# sch_AGV_Output.net
KiCad netlist of a schematic drawn in Altium Designer
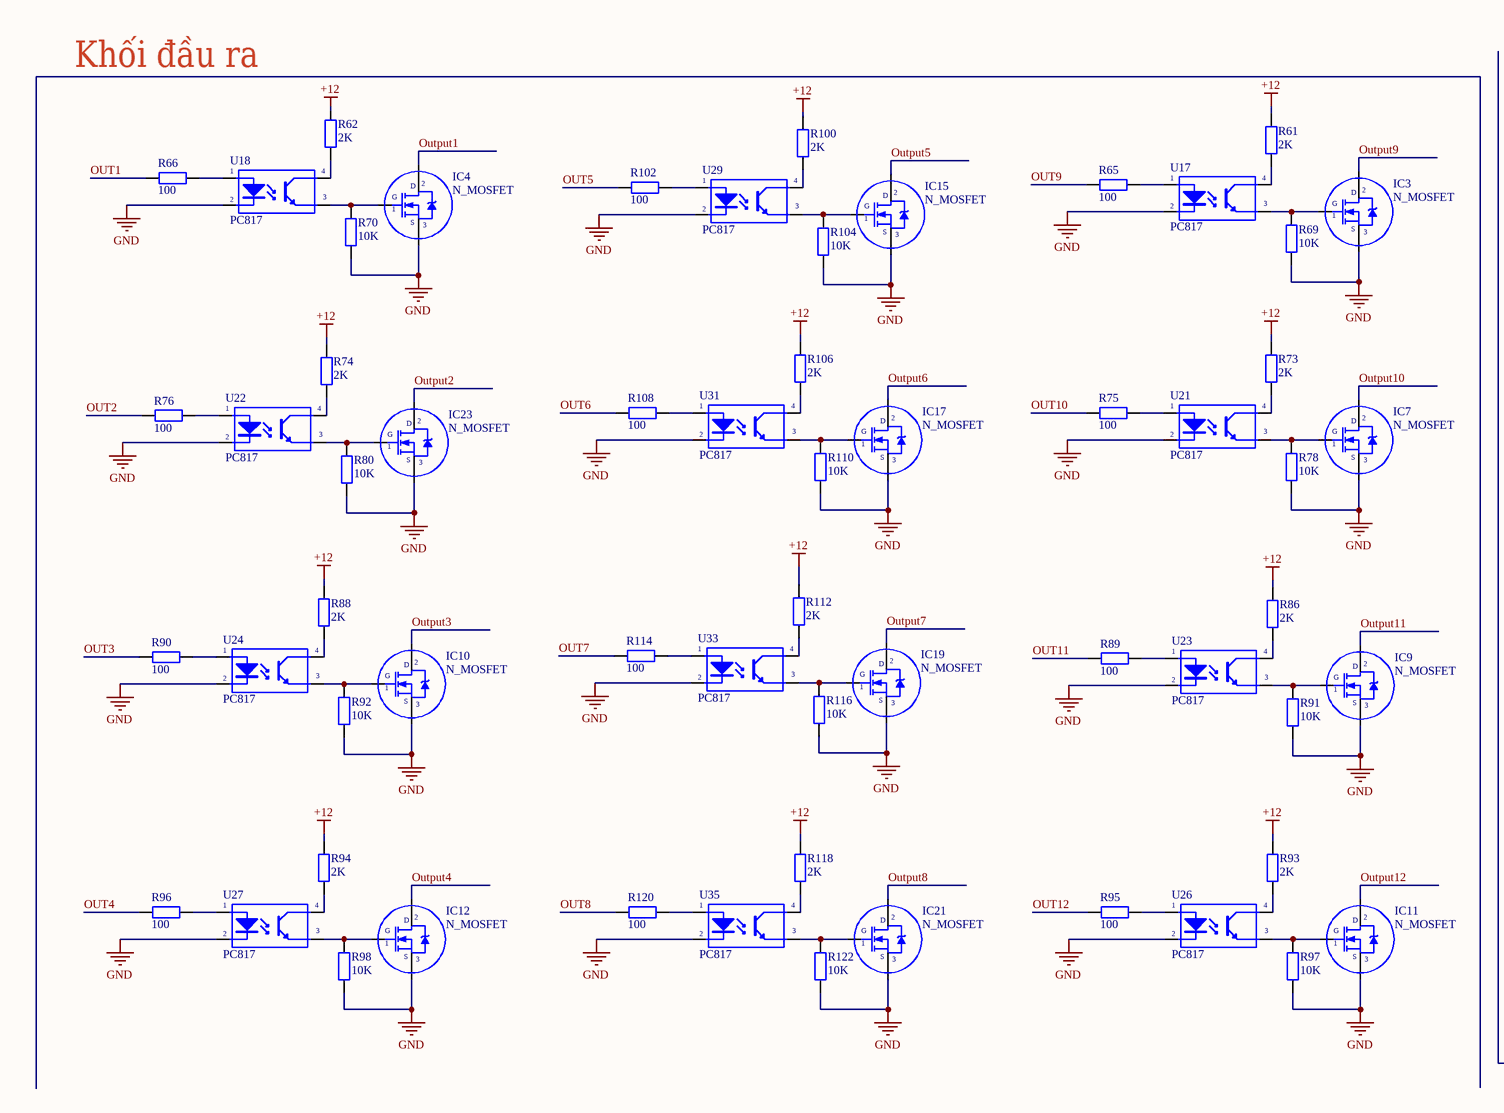
[diagram p0: sch_AGV_Output.SchDoc, left]
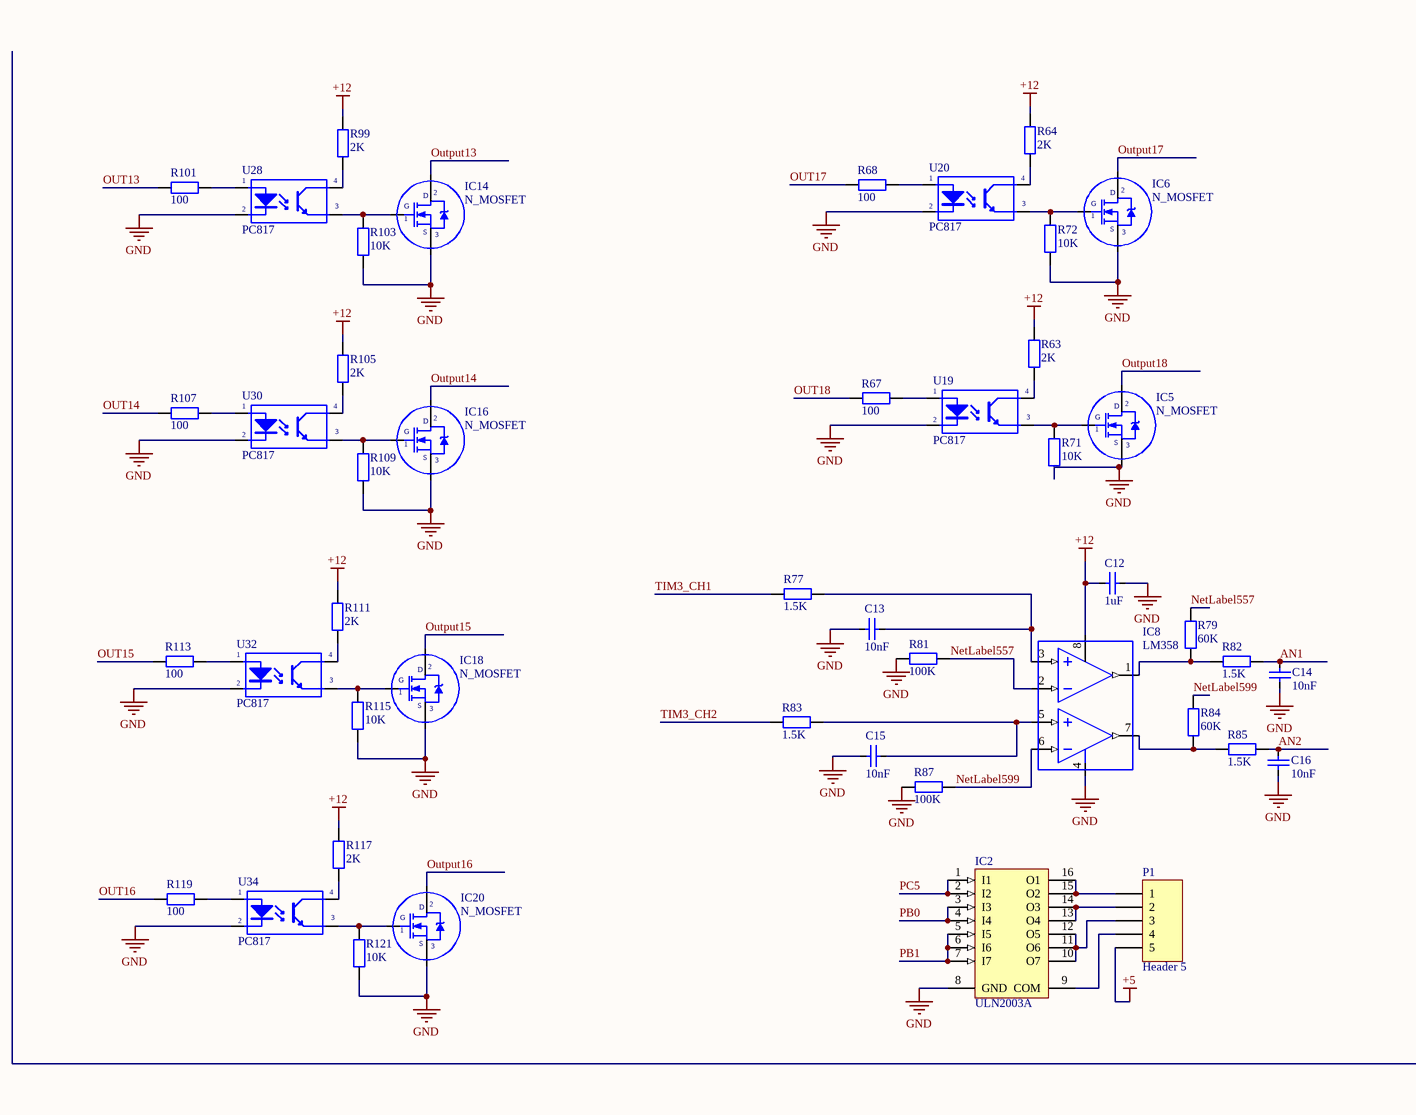
[diagram p1: sch_AGV_Output.SchDoc, right]

(export (version "E")
  (design (tool "Eeschema 10.0.6"))
  (components
    (comp (ref "C12")
      (value "1uF")
      (footprint "CAP_0805")
      (description "Capacitor")
      (fields (field (name "PUBLISHER") "Altium Limited"))
      (libsource (lib "schelib_AGVcontrol") (part "CapSMD"))
    )
    (comp (ref "C13")
      (value "10nF")
      (footprint "CAP_0805")
      (description "Capacitor")
      (fields (field (name "PUBLISHER") "Altium Limited"))
      (libsource (lib "schelib_AGVcontrol") (part "CapSMD"))
    )
    (comp (ref "C14")
      (value "10nF")
      (footprint "CAP_0805")
      (description "Capacitor")
      (fields (field (name "PUBLISHER") "Altium Limited"))
      (libsource (lib "schelib_AGVcontrol") (part "CapSMD"))
    )
    (comp (ref "C15")
      (value "10nF")
      (footprint "CAP_0805")
      (description "Capacitor")
      (fields (field (name "PUBLISHER") "Altium Limited"))
      (libsource (lib "schelib_AGVcontrol") (part "CapSMD"))
    )
    (comp (ref "C16")
      (value "10nF")
      (footprint "CAP_0805")
      (description "Capacitor")
      (fields (field (name "PUBLISHER") "Altium Limited"))
      (libsource (lib "schelib_AGVcontrol") (part "CapSMD"))
    )
    (comp (ref "IC2")
      (value "ULN2003A")
      (footprint "SOIC16")
      (description "High-Voltage, High-Current Darlington Array")
      (fields (field (name "PUBLISHER") "Altium Limited"))
      (libsource (lib "schelib_AGVcontrol") (part "ULN2003A"))
    )
    (comp (ref "IC3")
      (value "N_MOSFET")
      (footprint "SOT23A")
      (description "Generic N Channel MOSFET")
      (libsource (lib "schelib_AGVcontrol") (part "MOSFET_N"))
    )
    (comp (ref "IC4")
      (value "N_MOSFET")
      (footprint "SOT23A")
      (description "Generic N Channel MOSFET")
      (libsource (lib "schelib_AGVcontrol") (part "MOSFET_N"))
    )
    (comp (ref "IC5")
      (value "N_MOSFET")
      (footprint "SOT23A")
      (description "Generic N Channel MOSFET")
      (libsource (lib "schelib_AGVcontrol") (part "MOSFET_N"))
    )
    (comp (ref "IC6")
      (value "N_MOSFET")
      (footprint "SOT23A")
      (description "Generic N Channel MOSFET")
      (libsource (lib "schelib_AGVcontrol") (part "MOSFET_N"))
    )
    (comp (ref "IC7")
      (value "N_MOSFET")
      (footprint "SOT23A")
      (description "Generic N Channel MOSFET")
      (libsource (lib "schelib_AGVcontrol") (part "MOSFET_N"))
    )
    (comp (ref "IC8")
      (value "LM358")
      (footprint "SOP8-PP")
      (description "Low-Power Dual Operational Amplifier")
      (libsource (lib "schelib_AGVcontrol") (part "LM358"))
    )
    (comp (ref "IC9")
      (value "N_MOSFET")
      (footprint "SOT23A")
      (description "Generic N Channel MOSFET")
      (libsource (lib "schelib_AGVcontrol") (part "MOSFET_N"))
    )
    (comp (ref "IC10")
      (value "N_MOSFET")
      (footprint "SOT23A")
      (description "Generic N Channel MOSFET")
      (libsource (lib "schelib_AGVcontrol") (part "MOSFET_N"))
    )
    (comp (ref "IC11")
      (value "N_MOSFET")
      (footprint "SOT23A")
      (description "Generic N Channel MOSFET")
      (libsource (lib "schelib_AGVcontrol") (part "MOSFET_N"))
    )
    (comp (ref "IC12")
      (value "N_MOSFET")
      (footprint "SOT23A")
      (description "Generic N Channel MOSFET")
      (libsource (lib "schelib_AGVcontrol") (part "MOSFET_N"))
    )
    (comp (ref "IC14")
      (value "N_MOSFET")
      (footprint "SOT23A")
      (description "Generic N Channel MOSFET")
      (libsource (lib "schelib_AGVcontrol") (part "MOSFET_N"))
    )
    (comp (ref "IC15")
      (value "N_MOSFET")
      (footprint "SOT23A")
      (description "Generic N Channel MOSFET")
      (libsource (lib "schelib_AGVcontrol") (part "MOSFET_N"))
    )
    (comp (ref "IC16")
      (value "N_MOSFET")
      (footprint "SOT23A")
      (description "Generic N Channel MOSFET")
      (libsource (lib "schelib_AGVcontrol") (part "MOSFET_N"))
    )
    (comp (ref "IC17")
      (value "N_MOSFET")
      (footprint "SOT23A")
      (description "Generic N Channel MOSFET")
      (libsource (lib "schelib_AGVcontrol") (part "MOSFET_N"))
    )
    (comp (ref "IC18")
      (value "N_MOSFET")
      (footprint "SOT23A")
      (description "Generic N Channel MOSFET")
      (libsource (lib "schelib_AGVcontrol") (part "MOSFET_N"))
    )
    (comp (ref "IC19")
      (value "N_MOSFET")
      (footprint "SOT23A")
      (description "Generic N Channel MOSFET")
      (libsource (lib "schelib_AGVcontrol") (part "MOSFET_N"))
    )
    (comp (ref "IC20")
      (value "N_MOSFET")
      (footprint "SOT23A")
      (description "Generic N Channel MOSFET")
      (libsource (lib "schelib_AGVcontrol") (part "MOSFET_N"))
    )
    (comp (ref "IC21")
      (value "N_MOSFET")
      (footprint "SOT23A")
      (description "Generic N Channel MOSFET")
      (libsource (lib "schelib_AGVcontrol") (part "MOSFET_N"))
    )
    (comp (ref "IC23")
      (value "N_MOSFET")
      (footprint "SOT23A")
      (description "Generic N Channel MOSFET")
      (libsource (lib "schelib_AGVcontrol") (part "MOSFET_N"))
    )
    (comp (ref "P1")
      (value "Header 5")
      (footprint "HDR5")
      (description "Header, 5-Pin")
      (fields (field (name "PUBLISHER") "Altium Limited"))
      (libsource (lib "schelib_AGVcontrol") (part "Header 5"))
    )
    (comp (ref "R61")
      (value "2K")
      (footprint "RES_SMD_0805")
      (description "Resistor")
      (fields
        (field (name "MANUFACTURER") "Generic Components")
        (field (name "PUBLISHER") "Altium Hobart Technology Centre")
      )
      (libsource (lib "schelib_AGVcontrol") (part "Res"))
    )
    (comp (ref "R62")
      (value "2K")
      (footprint "RES_SMD_0805")
      (description "Resistor")
      (fields
        (field (name "MANUFACTURER") "Generic Components")
        (field (name "PUBLISHER") "Altium Hobart Technology Centre")
      )
      (libsource (lib "schelib_AGVcontrol") (part "Res"))
    )
    (comp (ref "R63")
      (value "2K")
      (footprint "RES_SMD_0805")
      (description "Resistor")
      (fields
        (field (name "MANUFACTURER") "Generic Components")
        (field (name "PUBLISHER") "Altium Hobart Technology Centre")
      )
      (libsource (lib "schelib_AGVcontrol") (part "Res"))
    )
    (comp (ref "R64")
      (value "2K")
      (footprint "RES_SMD_0805")
      (description "Resistor")
      (fields
        (field (name "MANUFACTURER") "Generic Components")
        (field (name "PUBLISHER") "Altium Hobart Technology Centre")
      )
      (libsource (lib "schelib_AGVcontrol") (part "Res"))
    )
    (comp (ref "R65")
      (value "100")
      (footprint "RES_SMD_0805")
      (description "Resistor")
      (fields
        (field (name "MANUFACTURER") "Generic Components")
        (field (name "PUBLISHER") "Altium Hobart Technology Centre")
      )
      (libsource (lib "schelib_AGVcontrol") (part "Res"))
    )
    (comp (ref "R66")
      (value "100")
      (footprint "RES_SMD_0805")
      (description "Resistor")
      (fields
        (field (name "MANUFACTURER") "Generic Components")
        (field (name "PUBLISHER") "Altium Hobart Technology Centre")
      )
      (libsource (lib "schelib_AGVcontrol") (part "Res"))
    )
    (comp (ref "R67")
      (value "100")
      (footprint "RES_SMD_0805")
      (description "Resistor")
      (fields
        (field (name "MANUFACTURER") "Generic Components")
        (field (name "PUBLISHER") "Altium Hobart Technology Centre")
      )
      (libsource (lib "schelib_AGVcontrol") (part "Res"))
    )
    (comp (ref "R68")
      (value "100")
      (footprint "RES_SMD_0805")
      (description "Resistor")
      (fields
        (field (name "MANUFACTURER") "Generic Components")
        (field (name "PUBLISHER") "Altium Hobart Technology Centre")
      )
      (libsource (lib "schelib_AGVcontrol") (part "Res"))
    )
    (comp (ref "R69")
      (value "10K")
      (footprint "RES_SMD_0805")
      (description "Resistor")
      (fields
        (field (name "MANUFACTURER") "Generic Components")
        (field (name "PUBLISHER") "Altium Hobart Technology Centre")
      )
      (libsource (lib "schelib_AGVcontrol") (part "Res"))
    )
    (comp (ref "R70")
      (value "10K")
      (footprint "RES_SMD_0805")
      (description "Resistor")
      (fields
        (field (name "MANUFACTURER") "Generic Components")
        (field (name "PUBLISHER") "Altium Hobart Technology Centre")
      )
      (libsource (lib "schelib_AGVcontrol") (part "Res"))
    )
    (comp (ref "R71")
      (value "10K")
      (footprint "RES_SMD_0805")
      (description "Resistor")
      (fields
        (field (name "MANUFACTURER") "Generic Components")
        (field (name "PUBLISHER") "Altium Hobart Technology Centre")
      )
      (libsource (lib "schelib_AGVcontrol") (part "Res"))
    )
    (comp (ref "R72")
      (value "10K")
      (footprint "RES_SMD_0805")
      (description "Resistor")
      (fields
        (field (name "MANUFACTURER") "Generic Components")
        (field (name "PUBLISHER") "Altium Hobart Technology Centre")
      )
      (libsource (lib "schelib_AGVcontrol") (part "Res"))
    )
    (comp (ref "R73")
      (value "2K")
      (footprint "RES_SMD_0805")
      (description "Resistor")
      (fields
        (field (name "MANUFACTURER") "Generic Components")
        (field (name "PUBLISHER") "Altium Hobart Technology Centre")
      )
      (libsource (lib "schelib_AGVcontrol") (part "Res"))
    )
    (comp (ref "R74")
      (value "2K")
      (footprint "RES_SMD_0805")
      (description "Resistor")
      (fields
        (field (name "MANUFACTURER") "Generic Components")
        (field (name "PUBLISHER") "Altium Hobart Technology Centre")
      )
      (libsource (lib "schelib_AGVcontrol") (part "Res"))
    )
    (comp (ref "R75")
      (value "100")
      (footprint "RES_SMD_0805")
      (description "Resistor")
      (fields
        (field (name "MANUFACTURER") "Generic Components")
        (field (name "PUBLISHER") "Altium Hobart Technology Centre")
      )
      (libsource (lib "schelib_AGVcontrol") (part "Res"))
    )
    (comp (ref "R76")
      (value "100")
      (footprint "RES_SMD_0805")
      (description "Resistor")
      (fields
        (field (name "MANUFACTURER") "Generic Components")
        (field (name "PUBLISHER") "Altium Hobart Technology Centre")
      )
      (libsource (lib "schelib_AGVcontrol") (part "Res"))
    )
    (comp (ref "R77")
      (value "1.5K")
      (footprint "RES_SMD_0805")
      (description "Resistor")
      (fields
        (field (name "MANUFACTURER") "Generic Components")
        (field (name "PUBLISHER") "Altium Hobart Technology Centre")
      )
      (libsource (lib "schelib_AGVcontrol") (part "Res"))
    )
    (comp (ref "R78")
      (value "10K")
      (footprint "RES_SMD_0805")
      (description "Resistor")
      (fields
        (field (name "MANUFACTURER") "Generic Components")
        (field (name "PUBLISHER") "Altium Hobart Technology Centre")
      )
      (libsource (lib "schelib_AGVcontrol") (part "Res"))
    )
    (comp (ref "R79")
      (value "60K")
      (footprint "RES_SMD_0805")
      (description "Resistor")
      (fields
        (field (name "MANUFACTURER") "Generic Components")
        (field (name "PUBLISHER") "Altium Hobart Technology Centre")
      )
      (libsource (lib "schelib_AGVcontrol") (part "Res"))
    )
    (comp (ref "R80")
      (value "10K")
      (footprint "RES_SMD_0805")
      (description "Resistor")
      (fields
        (field (name "MANUFACTURER") "Generic Components")
        (field (name "PUBLISHER") "Altium Hobart Technology Centre")
      )
      (libsource (lib "schelib_AGVcontrol") (part "Res"))
    )
    (comp (ref "R81")
      (value "100K")
      (footprint "RES_SMD_0805")
      (description "Resistor")
      (fields
        (field (name "MANUFACTURER") "Generic Components")
        (field (name "PUBLISHER") "Altium Hobart Technology Centre")
      )
      (libsource (lib "schelib_AGVcontrol") (part "Res"))
    )
    (comp (ref "R82")
      (value "1.5K")
      (footprint "RES_SMD_0805")
      (description "Resistor")
      (fields
        (field (name "MANUFACTURER") "Generic Components")
        (field (name "PUBLISHER") "Altium Hobart Technology Centre")
      )
      (libsource (lib "schelib_AGVcontrol") (part "Res"))
    )
    (comp (ref "R83")
      (value "1.5K")
      (footprint "RES_SMD_0805")
      (description "Resistor")
      (fields
        (field (name "MANUFACTURER") "Generic Components")
        (field (name "PUBLISHER") "Altium Hobart Technology Centre")
      )
      (libsource (lib "schelib_AGVcontrol") (part "Res"))
    )
    (comp (ref "R84")
      (value "60K")
      (footprint "RES_SMD_0805")
      (description "Resistor")
      (fields
        (field (name "MANUFACTURER") "Generic Components")
        (field (name "PUBLISHER") "Altium Hobart Technology Centre")
      )
      (libsource (lib "schelib_AGVcontrol") (part "Res"))
    )
    (comp (ref "R85")
      (value "1.5K")
      (footprint "RES_SMD_0805")
      (description "Resistor")
      (fields
        (field (name "MANUFACTURER") "Generic Components")
        (field (name "PUBLISHER") "Altium Hobart Technology Centre")
      )
      (libsource (lib "schelib_AGVcontrol") (part "Res"))
    )
    (comp (ref "R86")
      (value "2K")
      (footprint "RES_SMD_0805")
      (description "Resistor")
      (fields
        (field (name "MANUFACTURER") "Generic Components")
        (field (name "PUBLISHER") "Altium Hobart Technology Centre")
      )
      (libsource (lib "schelib_AGVcontrol") (part "Res"))
    )
    (comp (ref "R87")
      (value "100K")
      (footprint "RES_SMD_0805")
      (description "Resistor")
      (fields
        (field (name "MANUFACTURER") "Generic Components")
        (field (name "PUBLISHER") "Altium Hobart Technology Centre")
      )
      (libsource (lib "schelib_AGVcontrol") (part "Res"))
    )
    (comp (ref "R88")
      (value "2K")
      (footprint "RES_SMD_0805")
      (description "Resistor")
      (fields
        (field (name "MANUFACTURER") "Generic Components")
        (field (name "PUBLISHER") "Altium Hobart Technology Centre")
      )
      (libsource (lib "schelib_AGVcontrol") (part "Res"))
    )
    (comp (ref "R89")
      (value "100")
      (footprint "RES_SMD_0805")
      (description "Resistor")
      (fields
        (field (name "MANUFACTURER") "Generic Components")
        (field (name "PUBLISHER") "Altium Hobart Technology Centre")
      )
      (libsource (lib "schelib_AGVcontrol") (part "Res"))
    )
    (comp (ref "R90")
      (value "100")
      (footprint "RES_SMD_0805")
      (description "Resistor")
      (fields
        (field (name "MANUFACTURER") "Generic Components")
        (field (name "PUBLISHER") "Altium Hobart Technology Centre")
      )
      (libsource (lib "schelib_AGVcontrol") (part "Res"))
    )
    (comp (ref "R91")
      (value "10K")
      (footprint "RES_SMD_0805")
      (description "Resistor")
      (fields
        (field (name "MANUFACTURER") "Generic Components")
        (field (name "PUBLISHER") "Altium Hobart Technology Centre")
      )
      (libsource (lib "schelib_AGVcontrol") (part "Res"))
    )
    (comp (ref "R92")
      (value "10K")
      (footprint "RES_SMD_0805")
      (description "Resistor")
      (fields
        (field (name "MANUFACTURER") "Generic Components")
        (field (name "PUBLISHER") "Altium Hobart Technology Centre")
      )
      (libsource (lib "schelib_AGVcontrol") (part "Res"))
    )
    (comp (ref "R93")
      (value "2K")
      (footprint "RES_SMD_0805")
      (description "Resistor")
      (fields
        (field (name "MANUFACTURER") "Generic Components")
        (field (name "PUBLISHER") "Altium Hobart Technology Centre")
      )
      (libsource (lib "schelib_AGVcontrol") (part "Res"))
    )
    (comp (ref "R94")
      (value "2K")
      (footprint "RES_SMD_0805")
      (description "Resistor")
      (fields
        (field (name "MANUFACTURER") "Generic Components")
        (field (name "PUBLISHER") "Altium Hobart Technology Centre")
      )
      (libsource (lib "schelib_AGVcontrol") (part "Res"))
    )
    (comp (ref "R95")
      (value "100")
      (footprint "RES_SMD_0805")
      (description "Resistor")
      (fields
        (field (name "MANUFACTURER") "Generic Components")
        (field (name "PUBLISHER") "Altium Hobart Technology Centre")
      )
      (libsource (lib "schelib_AGVcontrol") (part "Res"))
    )
    (comp (ref "R96")
      (value "100")
      (footprint "RES_SMD_0805")
      (description "Resistor")
      (fields
        (field (name "MANUFACTURER") "Generic Components")
        (field (name "PUBLISHER") "Altium Hobart Technology Centre")
      )
      (libsource (lib "schelib_AGVcontrol") (part "Res"))
    )
    (comp (ref "R97")
      (value "10K")
      (footprint "RES_SMD_0805")
      (description "Resistor")
      (fields
        (field (name "MANUFACTURER") "Generic Components")
        (field (name "PUBLISHER") "Altium Hobart Technology Centre")
      )
      (libsource (lib "schelib_AGVcontrol") (part "Res"))
    )
    (comp (ref "R98")
      (value "10K")
      (footprint "RES_SMD_0805")
      (description "Resistor")
      (fields
        (field (name "MANUFACTURER") "Generic Components")
        (field (name "PUBLISHER") "Altium Hobart Technology Centre")
      )
      (libsource (lib "schelib_AGVcontrol") (part "Res"))
    )
    (comp (ref "R99")
      (value "2K")
      (footprint "RES_SMD_0805")
      (description "Resistor")
      (fields
        (field (name "MANUFACTURER") "Generic Components")
        (field (name "PUBLISHER") "Altium Hobart Technology Centre")
      )
      (libsource (lib "schelib_AGVcontrol") (part "Res"))
    )
    (comp (ref "R100")
      (value "2K")
      (footprint "RES_SMD_0805")
      (description "Resistor")
      (fields
        (field (name "MANUFACTURER") "Generic Components")
        (field (name "PUBLISHER") "Altium Hobart Technology Centre")
      )
      (libsource (lib "schelib_AGVcontrol") (part "Res"))
    )
    (comp (ref "R101")
      (value "100")
      (footprint "RES_SMD_0805")
      (description "Resistor")
      (fields
        (field (name "MANUFACTURER") "Generic Components")
        (field (name "PUBLISHER") "Altium Hobart Technology Centre")
      )
      (libsource (lib "schelib_AGVcontrol") (part "Res"))
    )
    (comp (ref "R102")
      (value "100")
      (footprint "RES_SMD_0805")
      (description "Resistor")
      (fields
        (field (name "MANUFACTURER") "Generic Components")
        (field (name "PUBLISHER") "Altium Hobart Technology Centre")
      )
      (libsource (lib "schelib_AGVcontrol") (part "Res"))
    )
    (comp (ref "R103")
      (value "10K")
      (footprint "RES_SMD_0805")
      (description "Resistor")
      (fields
        (field (name "MANUFACTURER") "Generic Components")
        (field (name "PUBLISHER") "Altium Hobart Technology Centre")
      )
      (libsource (lib "schelib_AGVcontrol") (part "Res"))
    )
    (comp (ref "R104")
      (value "10K")
      (footprint "RES_SMD_0805")
      (description "Resistor")
      (fields
        (field (name "MANUFACTURER") "Generic Components")
        (field (name "PUBLISHER") "Altium Hobart Technology Centre")
      )
      (libsource (lib "schelib_AGVcontrol") (part "Res"))
    )
    (comp (ref "R105")
      (value "2K")
      (footprint "RES_SMD_0805")
      (description "Resistor")
      (fields
        (field (name "MANUFACTURER") "Generic Components")
        (field (name "PUBLISHER") "Altium Hobart Technology Centre")
      )
      (libsource (lib "schelib_AGVcontrol") (part "Res"))
    )
    (comp (ref "R106")
      (value "2K")
      (footprint "RES_SMD_0805")
      (description "Resistor")
      (fields
        (field (name "MANUFACTURER") "Generic Components")
        (field (name "PUBLISHER") "Altium Hobart Technology Centre")
      )
      (libsource (lib "schelib_AGVcontrol") (part "Res"))
    )
    (comp (ref "R107")
      (value "100")
      (footprint "RES_SMD_0805")
      (description "Resistor")
      (fields
        (field (name "MANUFACTURER") "Generic Components")
        (field (name "PUBLISHER") "Altium Hobart Technology Centre")
      )
      (libsource (lib "schelib_AGVcontrol") (part "Res"))
    )
    (comp (ref "R108")
      (value "100")
      (footprint "RES_SMD_0805")
      (description "Resistor")
      (fields
        (field (name "MANUFACTURER") "Generic Components")
        (field (name "PUBLISHER") "Altium Hobart Technology Centre")
      )
      (libsource (lib "schelib_AGVcontrol") (part "Res"))
    )
    (comp (ref "R109")
      (value "10K")
      (footprint "RES_SMD_0805")
      (description "Resistor")
      (fields
        (field (name "MANUFACTURER") "Generic Components")
        (field (name "PUBLISHER") "Altium Hobart Technology Centre")
      )
      (libsource (lib "schelib_AGVcontrol") (part "Res"))
    )
    (comp (ref "R110")
      (value "10K")
      (footprint "RES_SMD_0805")
      (description "Resistor")
      (fields
        (field (name "MANUFACTURER") "Generic Components")
        (field (name "PUBLISHER") "Altium Hobart Technology Centre")
      )
      (libsource (lib "schelib_AGVcontrol") (part "Res"))
    )
    (comp (ref "R111")
      (value "2K")
      (footprint "RES_SMD_0805")
      (description "Resistor")
      (fields
        (field (name "MANUFACTURER") "Generic Components")
        (field (name "PUBLISHER") "Altium Hobart Technology Centre")
      )
      (libsource (lib "schelib_AGVcontrol") (part "Res"))
    )
    (comp (ref "R112")
      (value "2K")
      (footprint "RES_SMD_0805")
      (description "Resistor")
      (fields
        (field (name "MANUFACTURER") "Generic Components")
        (field (name "PUBLISHER") "Altium Hobart Technology Centre")
      )
      (libsource (lib "schelib_AGVcontrol") (part "Res"))
    )
    (comp (ref "R113")
      (value "100")
      (footprint "RES_SMD_0805")
      (description "Resistor")
      (fields
        (field (name "MANUFACTURER") "Generic Components")
        (field (name "PUBLISHER") "Altium Hobart Technology Centre")
      )
      (libsource (lib "schelib_AGVcontrol") (part "Res"))
    )
    (comp (ref "R114")
      (value "100")
      (footprint "RES_SMD_0805")
      (description "Resistor")
      (fields
        (field (name "MANUFACTURER") "Generic Components")
        (field (name "PUBLISHER") "Altium Hobart Technology Centre")
      )
      (libsource (lib "schelib_AGVcontrol") (part "Res"))
    )
    (comp (ref "R115")
      (value "10K")
      (footprint "RES_SMD_0805")
      (description "Resistor")
      (fields
        (field (name "MANUFACTURER") "Generic Components")
        (field (name "PUBLISHER") "Altium Hobart Technology Centre")
      )
      (libsource (lib "schelib_AGVcontrol") (part "Res"))
    )
    (comp (ref "R116")
      (value "10K")
      (footprint "RES_SMD_0805")
      (description "Resistor")
      (fields
        (field (name "MANUFACTURER") "Generic Components")
        (field (name "PUBLISHER") "Altium Hobart Technology Centre")
      )
      (libsource (lib "schelib_AGVcontrol") (part "Res"))
    )
    (comp (ref "R117")
      (value "2K")
      (footprint "RES_SMD_0805")
      (description "Resistor")
      (fields
        (field (name "MANUFACTURER") "Generic Components")
        (field (name "PUBLISHER") "Altium Hobart Technology Centre")
      )
      (libsource (lib "schelib_AGVcontrol") (part "Res"))
    )
    (comp (ref "R118")
      (value "2K")
      (footprint "RES_SMD_0805")
      (description "Resistor")
      (fields
        (field (name "MANUFACTURER") "Generic Components")
        (field (name "PUBLISHER") "Altium Hobart Technology Centre")
      )
      (libsource (lib "schelib_AGVcontrol") (part "Res"))
    )
    (comp (ref "R119")
      (value "100")
      (footprint "RES_SMD_0805")
      (description "Resistor")
      (fields
        (field (name "MANUFACTURER") "Generic Components")
        (field (name "PUBLISHER") "Altium Hobart Technology Centre")
      )
      (libsource (lib "schelib_AGVcontrol") (part "Res"))
    )
    (comp (ref "R120")
      (value "100")
      (footprint "RES_SMD_0805")
      (description "Resistor")
      (fields
        (field (name "MANUFACTURER") "Generic Components")
        (field (name "PUBLISHER") "Altium Hobart Technology Centre")
      )
      (libsource (lib "schelib_AGVcontrol") (part "Res"))
    )
    (comp (ref "R121")
      (value "10K")
      (footprint "RES_SMD_0805")
      (description "Resistor")
      (fields
        (field (name "MANUFACTURER") "Generic Components")
        (field (name "PUBLISHER") "Altium Hobart Technology Centre")
      )
      (libsource (lib "schelib_AGVcontrol") (part "Res"))
    )
    (comp (ref "R122")
      (value "10K")
      (footprint "RES_SMD_0805")
      (description "Resistor")
      (fields
        (field (name "MANUFACTURER") "Generic Components")
        (field (name "PUBLISHER") "Altium Hobart Technology Centre")
      )
      (libsource (lib "schelib_AGVcontrol") (part "Res"))
    )
    (comp (ref "U17")
      (value "PC817")
      (footprint "DIP4/W0.3")
      (description "Single Opto")
      (libsource (lib "schelib_AGVcontrol") (part "PC817"))
    )
    (comp (ref "U18")
      (value "PC817")
      (footprint "DIP4/W0.3")
      (description "Single Opto")
      (libsource (lib "schelib_AGVcontrol") (part "PC817"))
    )
    (comp (ref "U19")
      (value "PC817")
      (footprint "DIP4/W0.3")
      (description "Single Opto")
      (libsource (lib "schelib_AGVcontrol") (part "PC817"))
    )
    (comp (ref "U20")
      (value "PC817")
      (footprint "DIP4/W0.3")
      (description "Single Opto")
      (libsource (lib "schelib_AGVcontrol") (part "PC817"))
    )
    (comp (ref "U21")
      (value "PC817")
      (footprint "DIP4/W0.3")
      (description "Single Opto")
      (libsource (lib "schelib_AGVcontrol") (part "PC817"))
    )
    (comp (ref "U22")
      (value "PC817")
      (footprint "DIP4/W0.3")
      (description "Single Opto")
      (libsource (lib "schelib_AGVcontrol") (part "PC817"))
    )
    (comp (ref "U23")
      (value "PC817")
      (footprint "DIP4/W0.3")
      (description "Single Opto")
      (libsource (lib "schelib_AGVcontrol") (part "PC817"))
    )
    (comp (ref "U24")
      (value "PC817")
      (footprint "DIP4/W0.3")
      (description "Single Opto")
      (libsource (lib "schelib_AGVcontrol") (part "PC817"))
    )
    (comp (ref "U26")
      (value "PC817")
      (footprint "DIP4/W0.3")
      (description "Single Opto")
      (libsource (lib "schelib_AGVcontrol") (part "PC817"))
    )
    (comp (ref "U27")
      (value "PC817")
      (footprint "DIP4/W0.3")
      (description "Single Opto")
      (libsource (lib "schelib_AGVcontrol") (part "PC817"))
    )
    (comp (ref "U28")
      (value "PC817")
      (footprint "DIP4/W0.3")
      (description "Single Opto")
      (libsource (lib "schelib_AGVcontrol") (part "PC817"))
    )
    (comp (ref "U29")
      (value "PC817")
      (footprint "DIP4/W0.3")
      (description "Single Opto")
      (libsource (lib "schelib_AGVcontrol") (part "PC817"))
    )
    (comp (ref "U30")
      (value "PC817")
      (footprint "DIP4/W0.3")
      (description "Single Opto")
      (libsource (lib "schelib_AGVcontrol") (part "PC817"))
    )
    (comp (ref "U31")
      (value "PC817")
      (footprint "DIP4/W0.3")
      (description "Single Opto")
      (libsource (lib "schelib_AGVcontrol") (part "PC817"))
    )
    (comp (ref "U32")
      (value "PC817")
      (footprint "DIP4/W0.3")
      (description "Single Opto")
      (libsource (lib "schelib_AGVcontrol") (part "PC817"))
    )
    (comp (ref "U33")
      (value "PC817")
      (footprint "DIP4/W0.3")
      (description "Single Opto")
      (libsource (lib "schelib_AGVcontrol") (part "PC817"))
    )
    (comp (ref "U34")
      (value "PC817")
      (footprint "DIP4/W0.3")
      (description "Single Opto")
      (libsource (lib "schelib_AGVcontrol") (part "PC817"))
    )
    (comp (ref "U35")
      (value "PC817")
      (footprint "DIP4/W0.3")
      (description "Single Opto")
      (libsource (lib "schelib_AGVcontrol") (part "PC817"))
    )
  )
  (nets
    (net (code "1") (name "+5") (class "Default")
      (node (ref "P1") (pin "5") (pinfunction "5_5") (pintype "passive"))
    )
    (net (code "2") (name "+12") (class "Default")
      (node (ref "C12") (pin "1") (pinfunction "1_1") (pintype "passive"))
      (node (ref "IC8") (pin "8") (pinfunction "+V_8") (pintype "passive"))
      (node (ref "R100") (pin "1") (pinfunction "1_1") (pintype "passive"))
      (node (ref "R105") (pin "1") (pinfunction "1_1") (pintype "passive"))
      (node (ref "R106") (pin "1") (pinfunction "1_1") (pintype "passive"))
      (node (ref "R111") (pin "1") (pinfunction "1_1") (pintype "passive"))
      (node (ref "R112") (pin "1") (pinfunction "1_1") (pintype "passive"))
      (node (ref "R117") (pin "1") (pinfunction "1_1") (pintype "passive"))
      (node (ref "R118") (pin "1") (pinfunction "1_1") (pintype "passive"))
      (node (ref "R61") (pin "1") (pinfunction "1_1") (pintype "passive"))
      (node (ref "R62") (pin "1") (pinfunction "1_1") (pintype "passive"))
      (node (ref "R63") (pin "1") (pinfunction "1_1") (pintype "passive"))
      (node (ref "R64") (pin "1") (pinfunction "1_1") (pintype "passive"))
      (node (ref "R73") (pin "1") (pinfunction "1_1") (pintype "passive"))
      (node (ref "R74") (pin "1") (pinfunction "1_1") (pintype "passive"))
      (node (ref "R86") (pin "1") (pinfunction "1_1") (pintype "passive"))
      (node (ref "R88") (pin "1") (pinfunction "1_1") (pintype "passive"))
      (node (ref "R93") (pin "1") (pinfunction "1_1") (pintype "passive"))
      (node (ref "R94") (pin "1") (pinfunction "1_1") (pintype "passive"))
      (node (ref "R99") (pin "1") (pinfunction "1_1") (pintype "passive"))
    )
    (net (code "3") (name "/AN1") (class "Default")
      (node (ref "C14") (pin "2") (pinfunction "2_2") (pintype "passive"))
      (node (ref "R82") (pin "1") (pinfunction "1_1") (pintype "passive"))
    )
    (net (code "4") (name "/AN2") (class "Default")
      (node (ref "C16") (pin "2") (pinfunction "2_2") (pintype "passive"))
      (node (ref "R85") (pin "1") (pinfunction "1_1") (pintype "passive"))
    )
    (net (code "5") (name "/NetLabel557") (class "Default")
      (node (ref "IC8") (pin "2") (pinfunction "IN-_2") (pintype "input"))
      (node (ref "R79") (pin "1") (pinfunction "1_1") (pintype "passive"))
      (node (ref "R81") (pin "1") (pinfunction "1_1") (pintype "passive"))
    )
    (net (code "6") (name "/NetLabel599") (class "Default")
      (node (ref "IC8") (pin "6") (pinfunction "IN-_6") (pintype "input"))
      (node (ref "R84") (pin "1") (pinfunction "1_1") (pintype "passive"))
      (node (ref "R87") (pin "1") (pinfunction "1_1") (pintype "passive"))
    )
    (net (code "7") (name "/OUT1") (class "Default")
      (node (ref "R66") (pin "2") (pinfunction "2_2") (pintype "passive"))
    )
    (net (code "8") (name "/OUT2") (class "Default")
      (node (ref "R76") (pin "2") (pinfunction "2_2") (pintype "passive"))
    )
    (net (code "9") (name "/OUT3") (class "Default")
      (node (ref "R90") (pin "2") (pinfunction "2_2") (pintype "passive"))
    )
    (net (code "10") (name "/OUT4") (class "Default")
      (node (ref "R96") (pin "2") (pinfunction "2_2") (pintype "passive"))
    )
    (net (code "11") (name "/OUT5") (class "Default")
      (node (ref "R102") (pin "2") (pinfunction "2_2") (pintype "passive"))
    )
    (net (code "12") (name "/OUT6") (class "Default")
      (node (ref "R108") (pin "2") (pinfunction "2_2") (pintype "passive"))
    )
    (net (code "13") (name "/OUT7") (class "Default")
      (node (ref "R114") (pin "2") (pinfunction "2_2") (pintype "passive"))
    )
    (net (code "14") (name "/OUT8") (class "Default")
      (node (ref "R120") (pin "2") (pinfunction "2_2") (pintype "passive"))
    )
    (net (code "15") (name "/OUT9") (class "Default")
      (node (ref "R65") (pin "2") (pinfunction "2_2") (pintype "passive"))
    )
    (net (code "16") (name "/OUT10") (class "Default")
      (node (ref "R75") (pin "2") (pinfunction "2_2") (pintype "passive"))
    )
    (net (code "17") (name "/OUT11") (class "Default")
      (node (ref "R89") (pin "2") (pinfunction "2_2") (pintype "passive"))
    )
    (net (code "18") (name "/OUT12") (class "Default")
      (node (ref "R95") (pin "2") (pinfunction "2_2") (pintype "passive"))
    )
    (net (code "19") (name "/OUT13") (class "Default")
      (node (ref "R101") (pin "2") (pinfunction "2_2") (pintype "passive"))
    )
    (net (code "20") (name "/OUT14") (class "Default")
      (node (ref "R107") (pin "2") (pinfunction "2_2") (pintype "passive"))
    )
    (net (code "21") (name "/OUT15") (class "Default")
      (node (ref "R113") (pin "2") (pinfunction "2_2") (pintype "passive"))
    )
    (net (code "22") (name "/OUT16") (class "Default")
      (node (ref "R119") (pin "2") (pinfunction "2_2") (pintype "passive"))
    )
    (net (code "23") (name "/OUT17") (class "Default")
      (node (ref "R68") (pin "2") (pinfunction "2_2") (pintype "passive"))
    )
    (net (code "24") (name "/OUT18") (class "Default")
      (node (ref "R67") (pin "2") (pinfunction "2_2") (pintype "passive"))
    )
    (net (code "25") (name "/Output1") (class "Default")
      (node (ref "IC4") (pin "2") (pinfunction "D_2") (pintype "passive"))
    )
    (net (code "26") (name "/Output2") (class "Default")
      (node (ref "IC23") (pin "2") (pinfunction "D_2") (pintype "passive"))
    )
    (net (code "27") (name "/Output3") (class "Default")
      (node (ref "IC10") (pin "2") (pinfunction "D_2") (pintype "passive"))
    )
    (net (code "28") (name "/Output4") (class "Default")
      (node (ref "IC12") (pin "2") (pinfunction "D_2") (pintype "passive"))
    )
    (net (code "29") (name "/Output5") (class "Default")
      (node (ref "IC15") (pin "2") (pinfunction "D_2") (pintype "passive"))
    )
    (net (code "30") (name "/Output6") (class "Default")
      (node (ref "IC17") (pin "2") (pinfunction "D_2") (pintype "passive"))
    )
    (net (code "31") (name "/Output7") (class "Default")
      (node (ref "IC19") (pin "2") (pinfunction "D_2") (pintype "passive"))
    )
    (net (code "32") (name "/Output8") (class "Default")
      (node (ref "IC21") (pin "2") (pinfunction "D_2") (pintype "passive"))
    )
    (net (code "33") (name "/Output9") (class "Default")
      (node (ref "IC3") (pin "2") (pinfunction "D_2") (pintype "passive"))
    )
    (net (code "34") (name "/Output10") (class "Default")
      (node (ref "IC7") (pin "2") (pinfunction "D_2") (pintype "passive"))
    )
    (net (code "35") (name "/Output11") (class "Default")
      (node (ref "IC9") (pin "2") (pinfunction "D_2") (pintype "passive"))
    )
    (net (code "36") (name "/Output12") (class "Default")
      (node (ref "IC11") (pin "2") (pinfunction "D_2") (pintype "passive"))
    )
    (net (code "37") (name "/Output13") (class "Default")
      (node (ref "IC14") (pin "2") (pinfunction "D_2") (pintype "passive"))
    )
    (net (code "38") (name "/Output14") (class "Default")
      (node (ref "IC16") (pin "2") (pinfunction "D_2") (pintype "passive"))
    )
    (net (code "39") (name "/Output15") (class "Default")
      (node (ref "IC18") (pin "2") (pinfunction "D_2") (pintype "passive"))
    )
    (net (code "40") (name "/Output16") (class "Default")
      (node (ref "IC20") (pin "2") (pinfunction "D_2") (pintype "passive"))
    )
    (net (code "41") (name "/Output17") (class "Default")
      (node (ref "IC6") (pin "2") (pinfunction "D_2") (pintype "passive"))
    )
    (net (code "42") (name "/Output18") (class "Default")
      (node (ref "IC5") (pin "2") (pinfunction "D_2") (pintype "passive"))
    )
    (net (code "43") (name "/PB0") (class "Default")
      (node (ref "IC2") (pin "3") (pinfunction "I3_3") (pintype "input"))
      (node (ref "IC2") (pin "4") (pinfunction "I4_4") (pintype "input"))
    )
    (net (code "44") (name "/PB1") (class "Default")
      (node (ref "IC2") (pin "5") (pinfunction "I5_5") (pintype "input"))
      (node (ref "IC2") (pin "6") (pinfunction "I6_6") (pintype "input"))
      (node (ref "IC2") (pin "7") (pinfunction "I7_7") (pintype "input"))
    )
    (net (code "45") (name "/PC5") (class "Default")
      (node (ref "IC2") (pin "1") (pinfunction "I1_1") (pintype "input"))
      (node (ref "IC2") (pin "2") (pinfunction "I2_2") (pintype "input"))
    )
    (net (code "46") (name "/TIM3_CH1") (class "Default")
      (node (ref "R77") (pin "2") (pinfunction "2_2") (pintype "passive"))
    )
    (net (code "47") (name "/TIM3_CH2") (class "Default")
      (node (ref "R83") (pin "2") (pinfunction "2_2") (pintype "passive"))
    )
    (net (code "48") (name "GND") (class "Default")
      (node (ref "C12") (pin "2") (pinfunction "2_2") (pintype "passive"))
      (node (ref "C13") (pin "1") (pinfunction "1_1") (pintype "passive"))
      (node (ref "C14") (pin "1") (pinfunction "1_1") (pintype "passive"))
      (node (ref "C15") (pin "1") (pinfunction "1_1") (pintype "passive"))
      (node (ref "C16") (pin "1") (pinfunction "1_1") (pintype "passive"))
      (node (ref "IC10") (pin "3") (pinfunction "S_3") (pintype "passive"))
      (node (ref "IC11") (pin "3") (pinfunction "S_3") (pintype "passive"))
      (node (ref "IC12") (pin "3") (pinfunction "S_3") (pintype "passive"))
      (node (ref "IC14") (pin "3") (pinfunction "S_3") (pintype "passive"))
      (node (ref "IC15") (pin "3") (pinfunction "S_3") (pintype "passive"))
      (node (ref "IC16") (pin "3") (pinfunction "S_3") (pintype "passive"))
      (node (ref "IC17") (pin "3") (pinfunction "S_3") (pintype "passive"))
      (node (ref "IC18") (pin "3") (pinfunction "S_3") (pintype "passive"))
      (node (ref "IC19") (pin "3") (pinfunction "S_3") (pintype "passive"))
      (node (ref "IC2") (pin "8") (pinfunction "GND_8") (pintype "power_in"))
      (node (ref "IC20") (pin "3") (pinfunction "S_3") (pintype "passive"))
      (node (ref "IC21") (pin "3") (pinfunction "S_3") (pintype "passive"))
      (node (ref "IC23") (pin "3") (pinfunction "S_3") (pintype "passive"))
      (node (ref "IC3") (pin "3") (pinfunction "S_3") (pintype "passive"))
      (node (ref "IC4") (pin "3") (pinfunction "S_3") (pintype "passive"))
      (node (ref "IC5") (pin "3") (pinfunction "S_3") (pintype "passive"))
      (node (ref "IC6") (pin "3") (pinfunction "S_3") (pintype "passive"))
      (node (ref "IC7") (pin "3") (pinfunction "S_3") (pintype "passive"))
      (node (ref "IC8") (pin "4") (pinfunction "-V_4") (pintype "passive"))
      (node (ref "IC9") (pin "3") (pinfunction "S_3") (pintype "passive"))
      (node (ref "R103") (pin "2") (pinfunction "2_2") (pintype "passive"))
      (node (ref "R104") (pin "2") (pinfunction "2_2") (pintype "passive"))
      (node (ref "R109") (pin "2") (pinfunction "2_2") (pintype "passive"))
      (node (ref "R110") (pin "2") (pinfunction "2_2") (pintype "passive"))
      (node (ref "R115") (pin "2") (pinfunction "2_2") (pintype "passive"))
      (node (ref "R116") (pin "2") (pinfunction "2_2") (pintype "passive"))
      (node (ref "R121") (pin "2") (pinfunction "2_2") (pintype "passive"))
      (node (ref "R122") (pin "2") (pinfunction "2_2") (pintype "passive"))
      (node (ref "R69") (pin "2") (pinfunction "2_2") (pintype "passive"))
      (node (ref "R70") (pin "2") (pinfunction "2_2") (pintype "passive"))
      (node (ref "R71") (pin "2") (pinfunction "2_2") (pintype "passive"))
      (node (ref "R72") (pin "2") (pinfunction "2_2") (pintype "passive"))
      (node (ref "R78") (pin "2") (pinfunction "2_2") (pintype "passive"))
      (node (ref "R80") (pin "2") (pinfunction "2_2") (pintype "passive"))
      (node (ref "R81") (pin "2") (pinfunction "2_2") (pintype "passive"))
      (node (ref "R87") (pin "2") (pinfunction "2_2") (pintype "passive"))
      (node (ref "R91") (pin "2") (pinfunction "2_2") (pintype "passive"))
      (node (ref "R92") (pin "2") (pinfunction "2_2") (pintype "passive"))
      (node (ref "R97") (pin "2") (pinfunction "2_2") (pintype "passive"))
      (node (ref "R98") (pin "2") (pinfunction "2_2") (pintype "passive"))
      (node (ref "U17") (pin "2") (pinfunction "K_2") (pintype "passive"))
      (node (ref "U18") (pin "2") (pinfunction "K_2") (pintype "passive"))
      (node (ref "U19") (pin "2") (pinfunction "K_2") (pintype "passive"))
      (node (ref "U20") (pin "2") (pinfunction "K_2") (pintype "passive"))
      (node (ref "U21") (pin "2") (pinfunction "K_2") (pintype "passive"))
      (node (ref "U22") (pin "2") (pinfunction "K_2") (pintype "passive"))
      (node (ref "U23") (pin "2") (pinfunction "K_2") (pintype "passive"))
      (node (ref "U24") (pin "2") (pinfunction "K_2") (pintype "passive"))
      (node (ref "U26") (pin "2") (pinfunction "K_2") (pintype "passive"))
      (node (ref "U27") (pin "2") (pinfunction "K_2") (pintype "passive"))
      (node (ref "U28") (pin "2") (pinfunction "K_2") (pintype "passive"))
      (node (ref "U29") (pin "2") (pinfunction "K_2") (pintype "passive"))
      (node (ref "U30") (pin "2") (pinfunction "K_2") (pintype "passive"))
      (node (ref "U31") (pin "2") (pinfunction "K_2") (pintype "passive"))
      (node (ref "U32") (pin "2") (pinfunction "K_2") (pintype "passive"))
      (node (ref "U33") (pin "2") (pinfunction "K_2") (pintype "passive"))
      (node (ref "U34") (pin "2") (pinfunction "K_2") (pintype "passive"))
      (node (ref "U35") (pin "2") (pinfunction "K_2") (pintype "passive"))
    )
    (net (code "49") (name "Net-(C13-Pad2)") (class "Default")
      (node (ref "C13") (pin "2") (pinfunction "2_2") (pintype "passive"))
      (node (ref "IC8") (pin "3") (pinfunction "IN+_3") (pintype "input"))
      (node (ref "R77") (pin "1") (pinfunction "1_1") (pintype "passive"))
    )
    (net (code "50") (name "Net-(C15-Pad2)") (class "Default")
      (node (ref "C15") (pin "2") (pinfunction "2_2") (pintype "passive"))
      (node (ref "IC8") (pin "5") (pinfunction "IN+_5") (pintype "input"))
      (node (ref "R83") (pin "1") (pinfunction "1_1") (pintype "passive"))
    )
    (net (code "51") (name "Net-(IC2-COM)") (class "Default")
      (node (ref "IC2") (pin "9") (pinfunction "COM_9") (pintype "passive"))
      (node (ref "P1") (pin "4") (pinfunction "4_4") (pintype "passive"))
    )
    (net (code "52") (name "Net-(IC2-O1)") (class "Default")
      (node (ref "IC2") (pin "15") (pinfunction "O2_15") (pintype "open_collector"))
      (node (ref "IC2") (pin "16") (pinfunction "O1_16") (pintype "open_collector"))
      (node (ref "P1") (pin "1") (pinfunction "1_1") (pintype "passive"))
    )
    (net (code "53") (name "Net-(IC2-O3)") (class "Default")
      (node (ref "IC2") (pin "13") (pinfunction "O4_13") (pintype "open_collector"))
      (node (ref "IC2") (pin "14") (pinfunction "O3_14") (pintype "open_collector"))
      (node (ref "P1") (pin "2") (pinfunction "2_2") (pintype "passive"))
    )
    (net (code "54") (name "Net-(IC2-O5)") (class "Default")
      (node (ref "IC2") (pin "10") (pinfunction "O7_10") (pintype "open_collector"))
      (node (ref "IC2") (pin "11") (pinfunction "O6_11") (pintype "open_collector"))
      (node (ref "IC2") (pin "12") (pinfunction "O5_12") (pintype "open_collector"))
      (node (ref "P1") (pin "3") (pinfunction "3_3") (pintype "passive"))
    )
    (net (code "55") (name "Net-(IC3-G)") (class "Default")
      (node (ref "IC3") (pin "1") (pinfunction "G_1") (pintype "passive"))
      (node (ref "R69") (pin "1") (pinfunction "1_1") (pintype "passive"))
      (node (ref "U17") (pin "3") (pinfunction "E_3") (pintype "passive"))
    )
    (net (code "56") (name "Net-(IC4-G)") (class "Default")
      (node (ref "IC4") (pin "1") (pinfunction "G_1") (pintype "passive"))
      (node (ref "R70") (pin "1") (pinfunction "1_1") (pintype "passive"))
      (node (ref "U18") (pin "3") (pinfunction "E_3") (pintype "passive"))
    )
    (net (code "57") (name "Net-(IC5-G)") (class "Default")
      (node (ref "IC5") (pin "1") (pinfunction "G_1") (pintype "passive"))
      (node (ref "R71") (pin "1") (pinfunction "1_1") (pintype "passive"))
      (node (ref "U19") (pin "3") (pinfunction "E_3") (pintype "passive"))
    )
    (net (code "58") (name "Net-(IC6-G)") (class "Default")
      (node (ref "IC6") (pin "1") (pinfunction "G_1") (pintype "passive"))
      (node (ref "R72") (pin "1") (pinfunction "1_1") (pintype "passive"))
      (node (ref "U20") (pin "3") (pinfunction "E_3") (pintype "passive"))
    )
    (net (code "59") (name "Net-(IC7-G)") (class "Default")
      (node (ref "IC7") (pin "1") (pinfunction "G_1") (pintype "passive"))
      (node (ref "R78") (pin "1") (pinfunction "1_1") (pintype "passive"))
      (node (ref "U21") (pin "3") (pinfunction "E_3") (pintype "passive"))
    )
    (net (code "60") (name "Net-(IC8-OUT-Pad1)") (class "Default")
      (node (ref "IC8") (pin "1") (pinfunction "OUT_1") (pintype "output"))
      (node (ref "R79") (pin "2") (pinfunction "2_2") (pintype "passive"))
      (node (ref "R82") (pin "2") (pinfunction "2_2") (pintype "passive"))
    )
    (net (code "61") (name "Net-(IC8-OUT-Pad7)") (class "Default")
      (node (ref "IC8") (pin "7") (pinfunction "OUT_7") (pintype "output"))
      (node (ref "R84") (pin "2") (pinfunction "2_2") (pintype "passive"))
      (node (ref "R85") (pin "2") (pinfunction "2_2") (pintype "passive"))
    )
    (net (code "62") (name "Net-(IC9-G)") (class "Default")
      (node (ref "IC9") (pin "1") (pinfunction "G_1") (pintype "passive"))
      (node (ref "R91") (pin "1") (pinfunction "1_1") (pintype "passive"))
      (node (ref "U23") (pin "3") (pinfunction "E_3") (pintype "passive"))
    )
    (net (code "63") (name "Net-(IC10-G)") (class "Default")
      (node (ref "IC10") (pin "1") (pinfunction "G_1") (pintype "passive"))
      (node (ref "R92") (pin "1") (pinfunction "1_1") (pintype "passive"))
      (node (ref "U24") (pin "3") (pinfunction "E_3") (pintype "passive"))
    )
    (net (code "64") (name "Net-(IC11-G)") (class "Default")
      (node (ref "IC11") (pin "1") (pinfunction "G_1") (pintype "passive"))
      (node (ref "R97") (pin "1") (pinfunction "1_1") (pintype "passive"))
      (node (ref "U26") (pin "3") (pinfunction "E_3") (pintype "passive"))
    )
    (net (code "65") (name "Net-(IC12-G)") (class "Default")
      (node (ref "IC12") (pin "1") (pinfunction "G_1") (pintype "passive"))
      (node (ref "R98") (pin "1") (pinfunction "1_1") (pintype "passive"))
      (node (ref "U27") (pin "3") (pinfunction "E_3") (pintype "passive"))
    )
    (net (code "66") (name "Net-(IC14-G)") (class "Default")
      (node (ref "IC14") (pin "1") (pinfunction "G_1") (pintype "passive"))
      (node (ref "R103") (pin "1") (pinfunction "1_1") (pintype "passive"))
      (node (ref "U28") (pin "3") (pinfunction "E_3") (pintype "passive"))
    )
    (net (code "67") (name "Net-(IC15-G)") (class "Default")
      (node (ref "IC15") (pin "1") (pinfunction "G_1") (pintype "passive"))
      (node (ref "R104") (pin "1") (pinfunction "1_1") (pintype "passive"))
      (node (ref "U29") (pin "3") (pinfunction "E_3") (pintype "passive"))
    )
    (net (code "68") (name "Net-(IC16-G)") (class "Default")
      (node (ref "IC16") (pin "1") (pinfunction "G_1") (pintype "passive"))
      (node (ref "R109") (pin "1") (pinfunction "1_1") (pintype "passive"))
      (node (ref "U30") (pin "3") (pinfunction "E_3") (pintype "passive"))
    )
    (net (code "69") (name "Net-(IC17-G)") (class "Default")
      (node (ref "IC17") (pin "1") (pinfunction "G_1") (pintype "passive"))
      (node (ref "R110") (pin "1") (pinfunction "1_1") (pintype "passive"))
      (node (ref "U31") (pin "3") (pinfunction "E_3") (pintype "passive"))
    )
    (net (code "70") (name "Net-(IC18-G)") (class "Default")
      (node (ref "IC18") (pin "1") (pinfunction "G_1") (pintype "passive"))
      (node (ref "R115") (pin "1") (pinfunction "1_1") (pintype "passive"))
      (node (ref "U32") (pin "3") (pinfunction "E_3") (pintype "passive"))
    )
    (net (code "71") (name "Net-(IC19-G)") (class "Default")
      (node (ref "IC19") (pin "1") (pinfunction "G_1") (pintype "passive"))
      (node (ref "R116") (pin "1") (pinfunction "1_1") (pintype "passive"))
      (node (ref "U33") (pin "3") (pinfunction "E_3") (pintype "passive"))
    )
    (net (code "72") (name "Net-(IC20-G)") (class "Default")
      (node (ref "IC20") (pin "1") (pinfunction "G_1") (pintype "passive"))
      (node (ref "R121") (pin "1") (pinfunction "1_1") (pintype "passive"))
      (node (ref "U34") (pin "3") (pinfunction "E_3") (pintype "passive"))
    )
    (net (code "73") (name "Net-(IC21-G)") (class "Default")
      (node (ref "IC21") (pin "1") (pinfunction "G_1") (pintype "passive"))
      (node (ref "R122") (pin "1") (pinfunction "1_1") (pintype "passive"))
      (node (ref "U35") (pin "3") (pinfunction "E_3") (pintype "passive"))
    )
    (net (code "74") (name "Net-(IC23-G)") (class "Default")
      (node (ref "IC23") (pin "1") (pinfunction "G_1") (pintype "passive"))
      (node (ref "R80") (pin "1") (pinfunction "1_1") (pintype "passive"))
      (node (ref "U22") (pin "3") (pinfunction "E_3") (pintype "passive"))
    )
    (net (code "75") (name "Net-(U17-A)") (class "Default")
      (node (ref "R65") (pin "1") (pinfunction "1_1") (pintype "passive"))
      (node (ref "U17") (pin "1") (pinfunction "A_1") (pintype "passive"))
    )
    (net (code "76") (name "Net-(U17-C)") (class "Default")
      (node (ref "R61") (pin "2") (pinfunction "2_2") (pintype "passive"))
      (node (ref "U17") (pin "4") (pinfunction "C_4") (pintype "passive"))
    )
    (net (code "77") (name "Net-(U18-A)") (class "Default")
      (node (ref "R66") (pin "1") (pinfunction "1_1") (pintype "passive"))
      (node (ref "U18") (pin "1") (pinfunction "A_1") (pintype "passive"))
    )
    (net (code "78") (name "Net-(U18-C)") (class "Default")
      (node (ref "R62") (pin "2") (pinfunction "2_2") (pintype "passive"))
      (node (ref "U18") (pin "4") (pinfunction "C_4") (pintype "passive"))
    )
    (net (code "79") (name "Net-(U19-A)") (class "Default")
      (node (ref "R67") (pin "1") (pinfunction "1_1") (pintype "passive"))
      (node (ref "U19") (pin "1") (pinfunction "A_1") (pintype "passive"))
    )
    (net (code "80") (name "Net-(U19-C)") (class "Default")
      (node (ref "R63") (pin "2") (pinfunction "2_2") (pintype "passive"))
      (node (ref "U19") (pin "4") (pinfunction "C_4") (pintype "passive"))
    )
    (net (code "81") (name "Net-(U20-A)") (class "Default")
      (node (ref "R68") (pin "1") (pinfunction "1_1") (pintype "passive"))
      (node (ref "U20") (pin "1") (pinfunction "A_1") (pintype "passive"))
    )
    (net (code "82") (name "Net-(U20-C)") (class "Default")
      (node (ref "R64") (pin "2") (pinfunction "2_2") (pintype "passive"))
      (node (ref "U20") (pin "4") (pinfunction "C_4") (pintype "passive"))
    )
    (net (code "83") (name "Net-(U21-A)") (class "Default")
      (node (ref "R75") (pin "1") (pinfunction "1_1") (pintype "passive"))
      (node (ref "U21") (pin "1") (pinfunction "A_1") (pintype "passive"))
    )
    (net (code "84") (name "Net-(U21-C)") (class "Default")
      (node (ref "R73") (pin "2") (pinfunction "2_2") (pintype "passive"))
      (node (ref "U21") (pin "4") (pinfunction "C_4") (pintype "passive"))
    )
    (net (code "85") (name "Net-(U22-A)") (class "Default")
      (node (ref "R76") (pin "1") (pinfunction "1_1") (pintype "passive"))
      (node (ref "U22") (pin "1") (pinfunction "A_1") (pintype "passive"))
    )
    (net (code "86") (name "Net-(U22-C)") (class "Default")
      (node (ref "R74") (pin "2") (pinfunction "2_2") (pintype "passive"))
      (node (ref "U22") (pin "4") (pinfunction "C_4") (pintype "passive"))
    )
    (net (code "87") (name "Net-(U23-A)") (class "Default")
      (node (ref "R89") (pin "1") (pinfunction "1_1") (pintype "passive"))
      (node (ref "U23") (pin "1") (pinfunction "A_1") (pintype "passive"))
    )
    (net (code "88") (name "Net-(U23-C)") (class "Default")
      (node (ref "R86") (pin "2") (pinfunction "2_2") (pintype "passive"))
      (node (ref "U23") (pin "4") (pinfunction "C_4") (pintype "passive"))
    )
    (net (code "89") (name "Net-(U24-A)") (class "Default")
      (node (ref "R90") (pin "1") (pinfunction "1_1") (pintype "passive"))
      (node (ref "U24") (pin "1") (pinfunction "A_1") (pintype "passive"))
    )
    (net (code "90") (name "Net-(U24-C)") (class "Default")
      (node (ref "R88") (pin "2") (pinfunction "2_2") (pintype "passive"))
      (node (ref "U24") (pin "4") (pinfunction "C_4") (pintype "passive"))
    )
    (net (code "91") (name "Net-(U26-A)") (class "Default")
      (node (ref "R95") (pin "1") (pinfunction "1_1") (pintype "passive"))
      (node (ref "U26") (pin "1") (pinfunction "A_1") (pintype "passive"))
    )
    (net (code "92") (name "Net-(U26-C)") (class "Default")
      (node (ref "R93") (pin "2") (pinfunction "2_2") (pintype "passive"))
      (node (ref "U26") (pin "4") (pinfunction "C_4") (pintype "passive"))
    )
    (net (code "93") (name "Net-(U27-A)") (class "Default")
      (node (ref "R96") (pin "1") (pinfunction "1_1") (pintype "passive"))
      (node (ref "U27") (pin "1") (pinfunction "A_1") (pintype "passive"))
    )
    (net (code "94") (name "Net-(U27-C)") (class "Default")
      (node (ref "R94") (pin "2") (pinfunction "2_2") (pintype "passive"))
      (node (ref "U27") (pin "4") (pinfunction "C_4") (pintype "passive"))
    )
    (net (code "95") (name "Net-(U28-A)") (class "Default")
      (node (ref "R101") (pin "1") (pinfunction "1_1") (pintype "passive"))
      (node (ref "U28") (pin "1") (pinfunction "A_1") (pintype "passive"))
    )
    (net (code "96") (name "Net-(U28-C)") (class "Default")
      (node (ref "R99") (pin "2") (pinfunction "2_2") (pintype "passive"))
      (node (ref "U28") (pin "4") (pinfunction "C_4") (pintype "passive"))
    )
    (net (code "97") (name "Net-(U29-A)") (class "Default")
      (node (ref "R102") (pin "1") (pinfunction "1_1") (pintype "passive"))
      (node (ref "U29") (pin "1") (pinfunction "A_1") (pintype "passive"))
    )
    (net (code "98") (name "Net-(U29-C)") (class "Default")
      (node (ref "R100") (pin "2") (pinfunction "2_2") (pintype "passive"))
      (node (ref "U29") (pin "4") (pinfunction "C_4") (pintype "passive"))
    )
    (net (code "99") (name "Net-(U30-A)") (class "Default")
      (node (ref "R107") (pin "1") (pinfunction "1_1") (pintype "passive"))
      (node (ref "U30") (pin "1") (pinfunction "A_1") (pintype "passive"))
    )
    (net (code "100") (name "Net-(U30-C)") (class "Default")
      (node (ref "R105") (pin "2") (pinfunction "2_2") (pintype "passive"))
      (node (ref "U30") (pin "4") (pinfunction "C_4") (pintype "passive"))
    )
    (net (code "101") (name "Net-(U31-A)") (class "Default")
      (node (ref "R108") (pin "1") (pinfunction "1_1") (pintype "passive"))
      (node (ref "U31") (pin "1") (pinfunction "A_1") (pintype "passive"))
    )
    (net (code "102") (name "Net-(U31-C)") (class "Default")
      (node (ref "R106") (pin "2") (pinfunction "2_2") (pintype "passive"))
      (node (ref "U31") (pin "4") (pinfunction "C_4") (pintype "passive"))
    )
    (net (code "103") (name "Net-(U32-A)") (class "Default")
      (node (ref "R113") (pin "1") (pinfunction "1_1") (pintype "passive"))
      (node (ref "U32") (pin "1") (pinfunction "A_1") (pintype "passive"))
    )
    (net (code "104") (name "Net-(U32-C)") (class "Default")
      (node (ref "R111") (pin "2") (pinfunction "2_2") (pintype "passive"))
      (node (ref "U32") (pin "4") (pinfunction "C_4") (pintype "passive"))
    )
    (net (code "105") (name "Net-(U33-A)") (class "Default")
      (node (ref "R114") (pin "1") (pinfunction "1_1") (pintype "passive"))
      (node (ref "U33") (pin "1") (pinfunction "A_1") (pintype "passive"))
    )
    (net (code "106") (name "Net-(U33-C)") (class "Default")
      (node (ref "R112") (pin "2") (pinfunction "2_2") (pintype "passive"))
      (node (ref "U33") (pin "4") (pinfunction "C_4") (pintype "passive"))
    )
    (net (code "107") (name "Net-(U34-A)") (class "Default")
      (node (ref "R119") (pin "1") (pinfunction "1_1") (pintype "passive"))
      (node (ref "U34") (pin "1") (pinfunction "A_1") (pintype "passive"))
    )
    (net (code "108") (name "Net-(U34-C)") (class "Default")
      (node (ref "R117") (pin "2") (pinfunction "2_2") (pintype "passive"))
      (node (ref "U34") (pin "4") (pinfunction "C_4") (pintype "passive"))
    )
    (net (code "109") (name "Net-(U35-A)") (class "Default")
      (node (ref "R120") (pin "1") (pinfunction "1_1") (pintype "passive"))
      (node (ref "U35") (pin "1") (pinfunction "A_1") (pintype "passive"))
    )
    (net (code "110") (name "Net-(U35-C)") (class "Default")
      (node (ref "R118") (pin "2") (pinfunction "2_2") (pintype "passive"))
      (node (ref "U35") (pin "4") (pinfunction "C_4") (pintype "passive"))
    )
  )
)
